# DKBLE112_IO_Shield_v1_0.net
KiCad netlist of a schematic drawn in EAGLE
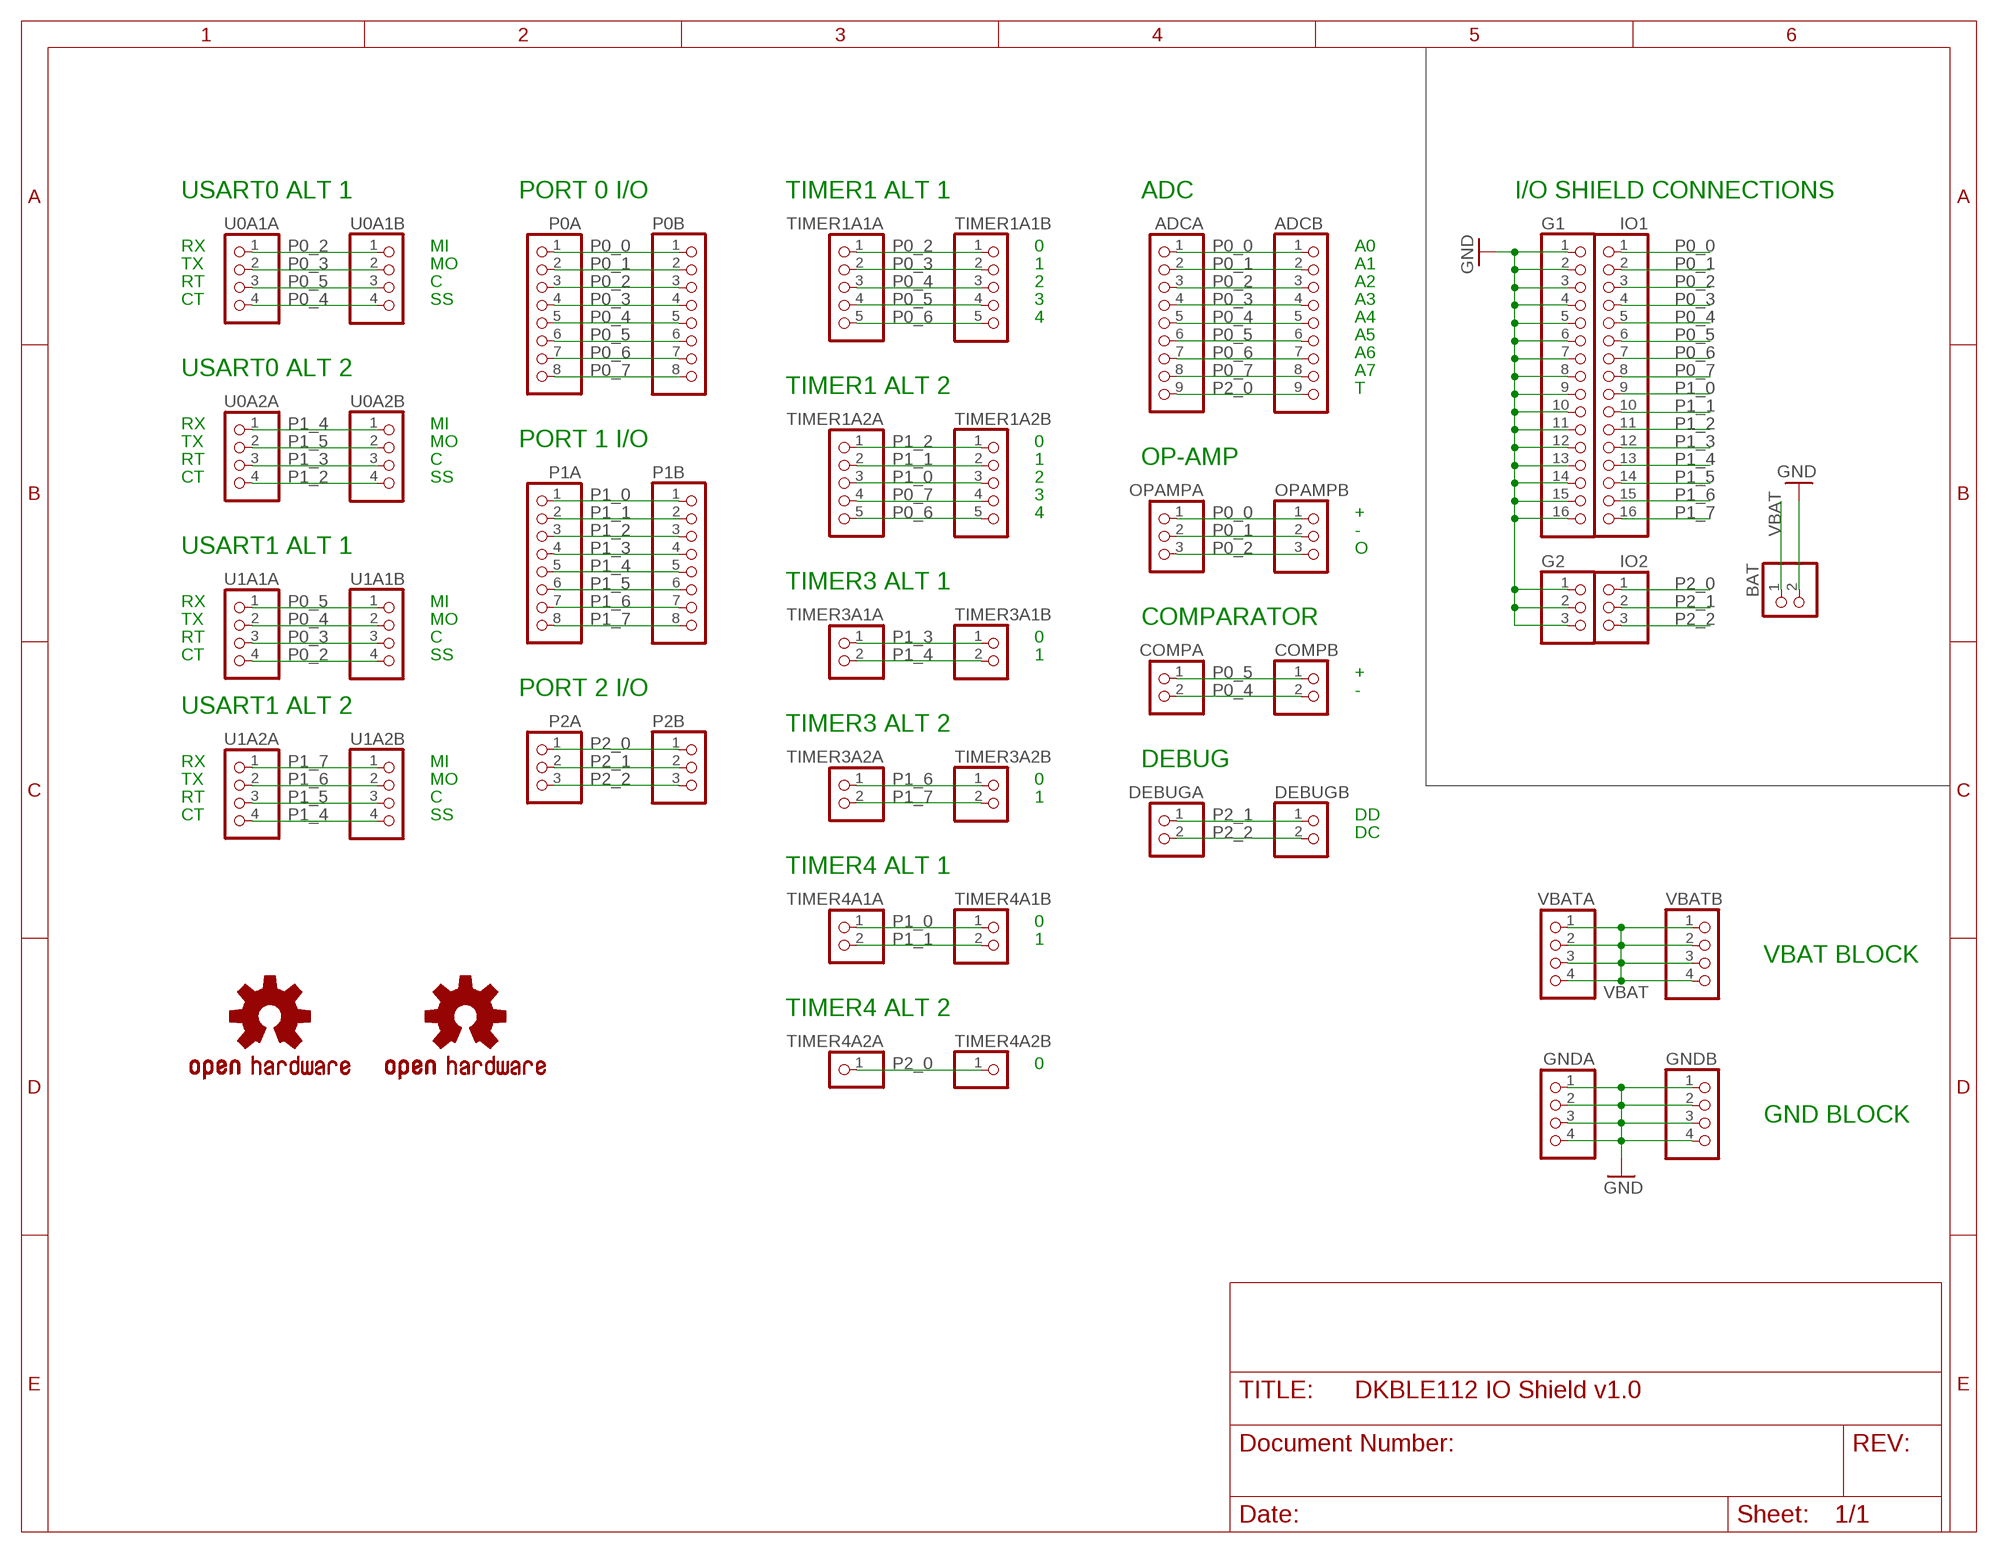
[diagram p0: schematic, sheet 1]

(export (version "E")
  (design (tool "Eeschema 10.0.6"))
  (components
    (comp (ref "ADCA")
      (value "PINHD-1X9")
      (footprint "eagle-import:1X09")
      (libsource (lib "eagle-import") (part "PINHD-1X9"))
    )
    (comp (ref "ADCB")
      (value "PINHD-1X9")
      (footprint "eagle-import:1X09")
      (libsource (lib "eagle-import") (part "PINHD-1X9"))
    )
    (comp (ref "BAT")
      (value "PINHD-1X2")
      (footprint "eagle-import:1X02")
      (libsource (lib "eagle-import") (part "PINHD-1X2"))
    )
    (comp (ref "COMPA")
      (value "PINHD-1X2")
      (footprint "eagle-import:1X02")
      (libsource (lib "eagle-import") (part "PINHD-1X2"))
    )
    (comp (ref "COMPB")
      (value "PINHD-1X2")
      (footprint "eagle-import:1X02")
      (libsource (lib "eagle-import") (part "PINHD-1X2"))
    )
    (comp (ref "DEBUGA")
      (value "PINHD-1X2")
      (footprint "eagle-import:1X02")
      (libsource (lib "eagle-import") (part "PINHD-1X2"))
    )
    (comp (ref "DEBUGB")
      (value "PINHD-1X2")
      (footprint "eagle-import:1X02")
      (libsource (lib "eagle-import") (part "PINHD-1X2"))
    )
    (comp (ref "G1")
      (value "PINHD-1X16")
      (footprint "eagle-import:1X16")
      (libsource (lib "eagle-import") (part "PINHD-1X16"))
    )
    (comp (ref "G2")
      (value "PINHD-1X3")
      (footprint "eagle-import:1X03")
      (libsource (lib "eagle-import") (part "PINHD-1X3"))
    )
    (comp (ref "GNDA")
      (value "PINHD-1X4")
      (footprint "eagle-import:1X04")
      (libsource (lib "eagle-import") (part "PINHD-1X4"))
    )
    (comp (ref "GNDB")
      (value "PINHD-1X4")
      (footprint "eagle-import:1X04")
      (libsource (lib "eagle-import") (part "PINHD-1X4"))
    )
    (comp (ref "IO1")
      (value "PINHD-1X16")
      (footprint "eagle-import:1X16")
      (libsource (lib "eagle-import") (part "PINHD-1X16"))
    )
    (comp (ref "IO2")
      (value "PINHD-1X3")
      (footprint "eagle-import:1X03")
      (libsource (lib "eagle-import") (part "PINHD-1X3"))
    )
    (comp (ref "OPAMPA")
      (value "PINHD-1X3")
      (footprint "eagle-import:1X03")
      (libsource (lib "eagle-import") (part "PINHD-1X3"))
    )
    (comp (ref "OPAMPB")
      (value "PINHD-1X3")
      (footprint "eagle-import:1X03")
      (libsource (lib "eagle-import") (part "PINHD-1X3"))
    )
    (comp (ref "P0A")
      (value "PINHD-1X8")
      (footprint "eagle-import:1X08")
      (libsource (lib "eagle-import") (part "PINHD-1X8"))
    )
    (comp (ref "P0B")
      (value "PINHD-1X8")
      (footprint "eagle-import:1X08")
      (libsource (lib "eagle-import") (part "PINHD-1X8"))
    )
    (comp (ref "P1A")
      (value "PINHD-1X8")
      (footprint "eagle-import:1X08")
      (libsource (lib "eagle-import") (part "PINHD-1X8"))
    )
    (comp (ref "P1B")
      (value "PINHD-1X8")
      (footprint "eagle-import:1X08")
      (libsource (lib "eagle-import") (part "PINHD-1X8"))
    )
    (comp (ref "P2A")
      (value "PINHD-1X3")
      (footprint "eagle-import:1X03")
      (libsource (lib "eagle-import") (part "PINHD-1X3"))
    )
    (comp (ref "P2B")
      (value "PINHD-1X3")
      (footprint "eagle-import:1X03")
      (libsource (lib "eagle-import") (part "PINHD-1X3"))
    )
    (comp (ref "TIMER1A1A")
      (value "PINHD-1X5")
      (footprint "eagle-import:1X05")
      (libsource (lib "eagle-import") (part "PINHD-1X5"))
    )
    (comp (ref "TIMER1A1B")
      (value "PINHD-1X5")
      (footprint "eagle-import:1X05")
      (libsource (lib "eagle-import") (part "PINHD-1X5"))
    )
    (comp (ref "TIMER1A2A")
      (value "PINHD-1X5")
      (footprint "eagle-import:1X05")
      (libsource (lib "eagle-import") (part "PINHD-1X5"))
    )
    (comp (ref "TIMER1A2B")
      (value "PINHD-1X5")
      (footprint "eagle-import:1X05")
      (libsource (lib "eagle-import") (part "PINHD-1X5"))
    )
    (comp (ref "TIMER3A1A")
      (value "PINHD-1X2")
      (footprint "eagle-import:1X02")
      (libsource (lib "eagle-import") (part "PINHD-1X2"))
    )
    (comp (ref "TIMER3A1B")
      (value "PINHD-1X2")
      (footprint "eagle-import:1X02")
      (libsource (lib "eagle-import") (part "PINHD-1X2"))
    )
    (comp (ref "TIMER3A2A")
      (value "PINHD-1X2")
      (footprint "eagle-import:1X02")
      (libsource (lib "eagle-import") (part "PINHD-1X2"))
    )
    (comp (ref "TIMER3A2B")
      (value "PINHD-1X2")
      (footprint "eagle-import:1X02")
      (libsource (lib "eagle-import") (part "PINHD-1X2"))
    )
    (comp (ref "TIMER4A1A")
      (value "PINHD-1X2")
      (footprint "eagle-import:1X02")
      (libsource (lib "eagle-import") (part "PINHD-1X2"))
    )
    (comp (ref "TIMER4A1B")
      (value "PINHD-1X2")
      (footprint "eagle-import:1X02")
      (libsource (lib "eagle-import") (part "PINHD-1X2"))
    )
    (comp (ref "TIMER4A2A")
      (value "PINHD-1X1")
      (footprint "eagle-import:1X01")
      (libsource (lib "eagle-import") (part "PINHD-1X1"))
    )
    (comp (ref "TIMER4A2B")
      (value "PINHD-1X1")
      (footprint "eagle-import:1X01")
      (libsource (lib "eagle-import") (part "PINHD-1X1"))
    )
    (comp (ref "U$1")
      (value "OSHW-LOGOL")
      (footprint "eagle-import:OSHW-LOGO-L")
      (libsource (lib "eagle-import") (part "OSHW-LOGOL"))
    )
    (comp (ref "U$2")
      (value "OSHW-LOGOM")
      (footprint "eagle-import:OSHW-LOGO-M")
      (libsource (lib "eagle-import") (part "OSHW-LOGOM"))
    )
    (comp (ref "U0A1A")
      (value "PINHD-1X4")
      (footprint "eagle-import:1X04")
      (libsource (lib "eagle-import") (part "PINHD-1X4"))
    )
    (comp (ref "U0A1B")
      (value "PINHD-1X4")
      (footprint "eagle-import:1X04")
      (libsource (lib "eagle-import") (part "PINHD-1X4"))
    )
    (comp (ref "U0A2A")
      (value "PINHD-1X4")
      (footprint "eagle-import:1X04")
      (libsource (lib "eagle-import") (part "PINHD-1X4"))
    )
    (comp (ref "U0A2B")
      (value "PINHD-1X4")
      (footprint "eagle-import:1X04")
      (libsource (lib "eagle-import") (part "PINHD-1X4"))
    )
    (comp (ref "U1A1A")
      (value "PINHD-1X4")
      (footprint "eagle-import:1X04")
      (libsource (lib "eagle-import") (part "PINHD-1X4"))
    )
    (comp (ref "U1A1B")
      (value "PINHD-1X4")
      (footprint "eagle-import:1X04")
      (libsource (lib "eagle-import") (part "PINHD-1X4"))
    )
    (comp (ref "U1A2A")
      (value "PINHD-1X4")
      (footprint "eagle-import:1X04")
      (libsource (lib "eagle-import") (part "PINHD-1X4"))
    )
    (comp (ref "U1A2B")
      (value "PINHD-1X4")
      (footprint "eagle-import:1X04")
      (libsource (lib "eagle-import") (part "PINHD-1X4"))
    )
    (comp (ref "VBATA")
      (value "PINHD-1X4")
      (footprint "eagle-import:1X04")
      (libsource (lib "eagle-import") (part "PINHD-1X4"))
    )
    (comp (ref "VBATB")
      (value "PINHD-1X4")
      (footprint "eagle-import:1X04")
      (libsource (lib "eagle-import") (part "PINHD-1X4"))
    )
  )
  (nets
    (net (code "1") (name "/P0_0") (class "Default")
      (node (ref "ADCA") (pin "1") (pinfunction "1_1") (pintype "passive"))
      (node (ref "ADCB") (pin "1") (pinfunction "1_1") (pintype "passive"))
      (node (ref "IO1") (pin "1") (pinfunction "1_1") (pintype "passive"))
      (node (ref "OPAMPA") (pin "1") (pinfunction "1_1") (pintype "passive"))
      (node (ref "OPAMPB") (pin "1") (pinfunction "1_1") (pintype "passive"))
      (node (ref "P0A") (pin "1") (pinfunction "1_1") (pintype "passive"))
      (node (ref "P0B") (pin "1") (pinfunction "1_1") (pintype "passive"))
    )
    (net (code "2") (name "/P0_1") (class "Default")
      (node (ref "ADCA") (pin "2") (pinfunction "2_2") (pintype "passive"))
      (node (ref "ADCB") (pin "2") (pinfunction "2_2") (pintype "passive"))
      (node (ref "IO1") (pin "2") (pinfunction "2_2") (pintype "passive"))
      (node (ref "OPAMPA") (pin "2") (pinfunction "2_2") (pintype "passive"))
      (node (ref "OPAMPB") (pin "2") (pinfunction "2_2") (pintype "passive"))
      (node (ref "P0A") (pin "2") (pinfunction "2_2") (pintype "passive"))
      (node (ref "P0B") (pin "2") (pinfunction "2_2") (pintype "passive"))
    )
    (net (code "3") (name "/P0_2") (class "Default")
      (node (ref "ADCA") (pin "3") (pinfunction "3_3") (pintype "passive"))
      (node (ref "ADCB") (pin "3") (pinfunction "3_3") (pintype "passive"))
      (node (ref "IO1") (pin "3") (pinfunction "3_3") (pintype "passive"))
      (node (ref "OPAMPA") (pin "3") (pinfunction "3_3") (pintype "passive"))
      (node (ref "OPAMPB") (pin "3") (pinfunction "3_3") (pintype "passive"))
      (node (ref "P0A") (pin "3") (pinfunction "3_3") (pintype "passive"))
      (node (ref "P0B") (pin "3") (pinfunction "3_3") (pintype "passive"))
      (node (ref "TIMER1A1A") (pin "1") (pinfunction "1_1") (pintype "passive"))
      (node (ref "TIMER1A1B") (pin "1") (pinfunction "1_1") (pintype "passive"))
      (node (ref "U0A1A") (pin "1") (pinfunction "1_1") (pintype "passive"))
      (node (ref "U0A1B") (pin "1") (pinfunction "1_1") (pintype "passive"))
      (node (ref "U1A1A") (pin "4") (pinfunction "4_4") (pintype "passive"))
      (node (ref "U1A1B") (pin "4") (pinfunction "4_4") (pintype "passive"))
    )
    (net (code "4") (name "/P0_3") (class "Default")
      (node (ref "ADCA") (pin "4") (pinfunction "4_4") (pintype "passive"))
      (node (ref "ADCB") (pin "4") (pinfunction "4_4") (pintype "passive"))
      (node (ref "IO1") (pin "4") (pinfunction "4_4") (pintype "passive"))
      (node (ref "P0A") (pin "4") (pinfunction "4_4") (pintype "passive"))
      (node (ref "P0B") (pin "4") (pinfunction "4_4") (pintype "passive"))
      (node (ref "TIMER1A1A") (pin "2") (pinfunction "2_2") (pintype "passive"))
      (node (ref "TIMER1A1B") (pin "2") (pinfunction "2_2") (pintype "passive"))
      (node (ref "U0A1A") (pin "2") (pinfunction "2_2") (pintype "passive"))
      (node (ref "U0A1B") (pin "2") (pinfunction "2_2") (pintype "passive"))
      (node (ref "U1A1A") (pin "3") (pinfunction "3_3") (pintype "passive"))
      (node (ref "U1A1B") (pin "3") (pinfunction "3_3") (pintype "passive"))
    )
    (net (code "5") (name "/P0_4") (class "Default")
      (node (ref "ADCA") (pin "5") (pinfunction "5_5") (pintype "passive"))
      (node (ref "ADCB") (pin "5") (pinfunction "5_5") (pintype "passive"))
      (node (ref "COMPA") (pin "2") (pinfunction "2_2") (pintype "passive"))
      (node (ref "COMPB") (pin "2") (pinfunction "2_2") (pintype "passive"))
      (node (ref "IO1") (pin "5") (pinfunction "5_5") (pintype "passive"))
      (node (ref "P0A") (pin "5") (pinfunction "5_5") (pintype "passive"))
      (node (ref "P0B") (pin "5") (pinfunction "5_5") (pintype "passive"))
      (node (ref "TIMER1A1A") (pin "3") (pinfunction "3_3") (pintype "passive"))
      (node (ref "TIMER1A1B") (pin "3") (pinfunction "3_3") (pintype "passive"))
      (node (ref "U0A1A") (pin "4") (pinfunction "4_4") (pintype "passive"))
      (node (ref "U0A1B") (pin "4") (pinfunction "4_4") (pintype "passive"))
      (node (ref "U1A1A") (pin "2") (pinfunction "2_2") (pintype "passive"))
      (node (ref "U1A1B") (pin "2") (pinfunction "2_2") (pintype "passive"))
    )
    (net (code "6") (name "/P0_5") (class "Default")
      (node (ref "ADCA") (pin "6") (pinfunction "6_6") (pintype "passive"))
      (node (ref "ADCB") (pin "6") (pinfunction "6_6") (pintype "passive"))
      (node (ref "COMPA") (pin "1") (pinfunction "1_1") (pintype "passive"))
      (node (ref "COMPB") (pin "1") (pinfunction "1_1") (pintype "passive"))
      (node (ref "IO1") (pin "6") (pinfunction "6_6") (pintype "passive"))
      (node (ref "P0A") (pin "6") (pinfunction "6_6") (pintype "passive"))
      (node (ref "P0B") (pin "6") (pinfunction "6_6") (pintype "passive"))
      (node (ref "TIMER1A1A") (pin "4") (pinfunction "4_4") (pintype "passive"))
      (node (ref "TIMER1A1B") (pin "4") (pinfunction "4_4") (pintype "passive"))
      (node (ref "U0A1A") (pin "3") (pinfunction "3_3") (pintype "passive"))
      (node (ref "U0A1B") (pin "3") (pinfunction "3_3") (pintype "passive"))
      (node (ref "U1A1A") (pin "1") (pinfunction "1_1") (pintype "passive"))
      (node (ref "U1A1B") (pin "1") (pinfunction "1_1") (pintype "passive"))
    )
    (net (code "7") (name "/P0_6") (class "Default")
      (node (ref "ADCA") (pin "7") (pinfunction "7_7") (pintype "passive"))
      (node (ref "ADCB") (pin "7") (pinfunction "7_7") (pintype "passive"))
      (node (ref "IO1") (pin "7") (pinfunction "7_7") (pintype "passive"))
      (node (ref "P0A") (pin "7") (pinfunction "7_7") (pintype "passive"))
      (node (ref "P0B") (pin "7") (pinfunction "7_7") (pintype "passive"))
      (node (ref "TIMER1A1A") (pin "5") (pinfunction "5_5") (pintype "passive"))
      (node (ref "TIMER1A1B") (pin "5") (pinfunction "5_5") (pintype "passive"))
      (node (ref "TIMER1A2A") (pin "5") (pinfunction "5_5") (pintype "passive"))
      (node (ref "TIMER1A2B") (pin "5") (pinfunction "5_5") (pintype "passive"))
    )
    (net (code "8") (name "/P0_7") (class "Default")
      (node (ref "ADCA") (pin "8") (pinfunction "8_8") (pintype "passive"))
      (node (ref "ADCB") (pin "8") (pinfunction "8_8") (pintype "passive"))
      (node (ref "IO1") (pin "8") (pinfunction "8_8") (pintype "passive"))
      (node (ref "P0A") (pin "8") (pinfunction "8_8") (pintype "passive"))
      (node (ref "P0B") (pin "8") (pinfunction "8_8") (pintype "passive"))
      (node (ref "TIMER1A2A") (pin "4") (pinfunction "4_4") (pintype "passive"))
      (node (ref "TIMER1A2B") (pin "4") (pinfunction "4_4") (pintype "passive"))
    )
    (net (code "9") (name "/P1_0") (class "Default")
      (node (ref "IO1") (pin "9") (pinfunction "9_9") (pintype "passive"))
      (node (ref "P1A") (pin "1") (pinfunction "1_1") (pintype "passive"))
      (node (ref "P1B") (pin "1") (pinfunction "1_1") (pintype "passive"))
      (node (ref "TIMER1A2A") (pin "3") (pinfunction "3_3") (pintype "passive"))
      (node (ref "TIMER1A2B") (pin "3") (pinfunction "3_3") (pintype "passive"))
      (node (ref "TIMER4A1A") (pin "1") (pinfunction "1_1") (pintype "passive"))
      (node (ref "TIMER4A1B") (pin "1") (pinfunction "1_1") (pintype "passive"))
    )
    (net (code "10") (name "/P1_1") (class "Default")
      (node (ref "IO1") (pin "10") (pinfunction "10_10") (pintype "passive"))
      (node (ref "P1A") (pin "2") (pinfunction "2_2") (pintype "passive"))
      (node (ref "P1B") (pin "2") (pinfunction "2_2") (pintype "passive"))
      (node (ref "TIMER1A2A") (pin "2") (pinfunction "2_2") (pintype "passive"))
      (node (ref "TIMER1A2B") (pin "2") (pinfunction "2_2") (pintype "passive"))
      (node (ref "TIMER4A1A") (pin "2") (pinfunction "2_2") (pintype "passive"))
      (node (ref "TIMER4A1B") (pin "2") (pinfunction "2_2") (pintype "passive"))
    )
    (net (code "11") (name "/P1_2") (class "Default")
      (node (ref "IO1") (pin "11") (pinfunction "11_11") (pintype "passive"))
      (node (ref "P1A") (pin "3") (pinfunction "3_3") (pintype "passive"))
      (node (ref "P1B") (pin "3") (pinfunction "3_3") (pintype "passive"))
      (node (ref "TIMER1A2A") (pin "1") (pinfunction "1_1") (pintype "passive"))
      (node (ref "TIMER1A2B") (pin "1") (pinfunction "1_1") (pintype "passive"))
      (node (ref "U0A2A") (pin "4") (pinfunction "4_4") (pintype "passive"))
      (node (ref "U0A2B") (pin "4") (pinfunction "4_4") (pintype "passive"))
    )
    (net (code "12") (name "/P1_3") (class "Default")
      (node (ref "IO1") (pin "12") (pinfunction "12_12") (pintype "passive"))
      (node (ref "P1A") (pin "4") (pinfunction "4_4") (pintype "passive"))
      (node (ref "P1B") (pin "4") (pinfunction "4_4") (pintype "passive"))
      (node (ref "TIMER3A1A") (pin "1") (pinfunction "1_1") (pintype "passive"))
      (node (ref "TIMER3A1B") (pin "1") (pinfunction "1_1") (pintype "passive"))
      (node (ref "U0A2A") (pin "3") (pinfunction "3_3") (pintype "passive"))
      (node (ref "U0A2B") (pin "3") (pinfunction "3_3") (pintype "passive"))
    )
    (net (code "13") (name "/P1_4") (class "Default")
      (node (ref "IO1") (pin "13") (pinfunction "13_13") (pintype "passive"))
      (node (ref "P1A") (pin "5") (pinfunction "5_5") (pintype "passive"))
      (node (ref "P1B") (pin "5") (pinfunction "5_5") (pintype "passive"))
      (node (ref "TIMER3A1A") (pin "2") (pinfunction "2_2") (pintype "passive"))
      (node (ref "TIMER3A1B") (pin "2") (pinfunction "2_2") (pintype "passive"))
      (node (ref "U0A2A") (pin "1") (pinfunction "1_1") (pintype "passive"))
      (node (ref "U0A2B") (pin "1") (pinfunction "1_1") (pintype "passive"))
      (node (ref "U1A2A") (pin "4") (pinfunction "4_4") (pintype "passive"))
      (node (ref "U1A2B") (pin "4") (pinfunction "4_4") (pintype "passive"))
    )
    (net (code "14") (name "/P1_5") (class "Default")
      (node (ref "IO1") (pin "14") (pinfunction "14_14") (pintype "passive"))
      (node (ref "P1A") (pin "6") (pinfunction "6_6") (pintype "passive"))
      (node (ref "P1B") (pin "6") (pinfunction "6_6") (pintype "passive"))
      (node (ref "U0A2A") (pin "2") (pinfunction "2_2") (pintype "passive"))
      (node (ref "U0A2B") (pin "2") (pinfunction "2_2") (pintype "passive"))
      (node (ref "U1A2A") (pin "3") (pinfunction "3_3") (pintype "passive"))
      (node (ref "U1A2B") (pin "3") (pinfunction "3_3") (pintype "passive"))
    )
    (net (code "15") (name "/P1_6") (class "Default")
      (node (ref "IO1") (pin "15") (pinfunction "15_15") (pintype "passive"))
      (node (ref "P1A") (pin "7") (pinfunction "7_7") (pintype "passive"))
      (node (ref "P1B") (pin "7") (pinfunction "7_7") (pintype "passive"))
      (node (ref "TIMER3A2A") (pin "1") (pinfunction "1_1") (pintype "passive"))
      (node (ref "TIMER3A2B") (pin "1") (pinfunction "1_1") (pintype "passive"))
      (node (ref "U1A2A") (pin "2") (pinfunction "2_2") (pintype "passive"))
      (node (ref "U1A2B") (pin "2") (pinfunction "2_2") (pintype "passive"))
    )
    (net (code "16") (name "/P1_7") (class "Default")
      (node (ref "IO1") (pin "16") (pinfunction "16_16") (pintype "passive"))
      (node (ref "P1A") (pin "8") (pinfunction "8_8") (pintype "passive"))
      (node (ref "P1B") (pin "8") (pinfunction "8_8") (pintype "passive"))
      (node (ref "TIMER3A2A") (pin "2") (pinfunction "2_2") (pintype "passive"))
      (node (ref "TIMER3A2B") (pin "2") (pinfunction "2_2") (pintype "passive"))
      (node (ref "U1A2A") (pin "1") (pinfunction "1_1") (pintype "passive"))
      (node (ref "U1A2B") (pin "1") (pinfunction "1_1") (pintype "passive"))
    )
    (net (code "17") (name "/P2_0") (class "Default")
      (node (ref "ADCA") (pin "9") (pinfunction "9_9") (pintype "passive"))
      (node (ref "ADCB") (pin "9") (pinfunction "9_9") (pintype "passive"))
      (node (ref "IO2") (pin "1") (pinfunction "1_1") (pintype "passive"))
      (node (ref "P2A") (pin "1") (pinfunction "1_1") (pintype "passive"))
      (node (ref "P2B") (pin "1") (pinfunction "1_1") (pintype "passive"))
      (node (ref "TIMER4A2A") (pin "1") (pinfunction "1_1") (pintype "passive"))
      (node (ref "TIMER4A2B") (pin "1") (pinfunction "1_1") (pintype "passive"))
    )
    (net (code "18") (name "/P2_1") (class "Default")
      (node (ref "DEBUGA") (pin "1") (pinfunction "1_1") (pintype "passive"))
      (node (ref "DEBUGB") (pin "1") (pinfunction "1_1") (pintype "passive"))
      (node (ref "IO2") (pin "2") (pinfunction "2_2") (pintype "passive"))
      (node (ref "P2A") (pin "2") (pinfunction "2_2") (pintype "passive"))
      (node (ref "P2B") (pin "2") (pinfunction "2_2") (pintype "passive"))
    )
    (net (code "19") (name "/P2_2") (class "Default")
      (node (ref "DEBUGA") (pin "2") (pinfunction "2_2") (pintype "passive"))
      (node (ref "DEBUGB") (pin "2") (pinfunction "2_2") (pintype "passive"))
      (node (ref "IO2") (pin "3") (pinfunction "3_3") (pintype "passive"))
      (node (ref "P2A") (pin "3") (pinfunction "3_3") (pintype "passive"))
      (node (ref "P2B") (pin "3") (pinfunction "3_3") (pintype "passive"))
    )
    (net (code "20") (name "/VBAT") (class "Default")
      (node (ref "BAT") (pin "1") (pinfunction "1_1") (pintype "passive"))
      (node (ref "VBATA") (pin "1") (pinfunction "1_1") (pintype "passive"))
      (node (ref "VBATA") (pin "2") (pinfunction "2_2") (pintype "passive"))
      (node (ref "VBATA") (pin "3") (pinfunction "3_3") (pintype "passive"))
      (node (ref "VBATA") (pin "4") (pinfunction "4_4") (pintype "passive"))
      (node (ref "VBATB") (pin "1") (pinfunction "1_1") (pintype "passive"))
      (node (ref "VBATB") (pin "2") (pinfunction "2_2") (pintype "passive"))
      (node (ref "VBATB") (pin "3") (pinfunction "3_3") (pintype "passive"))
      (node (ref "VBATB") (pin "4") (pinfunction "4_4") (pintype "passive"))
    )
    (net (code "21") (name "GND") (class "Default")
      (node (ref "BAT") (pin "2") (pinfunction "2_2") (pintype "passive"))
      (node (ref "G1") (pin "1") (pinfunction "1_1") (pintype "passive"))
      (node (ref "G1") (pin "10") (pinfunction "10_10") (pintype "passive"))
      (node (ref "G1") (pin "11") (pinfunction "11_11") (pintype "passive"))
      (node (ref "G1") (pin "12") (pinfunction "12_12") (pintype "passive"))
      (node (ref "G1") (pin "13") (pinfunction "13_13") (pintype "passive"))
      (node (ref "G1") (pin "14") (pinfunction "14_14") (pintype "passive"))
      (node (ref "G1") (pin "15") (pinfunction "15_15") (pintype "passive"))
      (node (ref "G1") (pin "16") (pinfunction "16_16") (pintype "passive"))
      (node (ref "G1") (pin "2") (pinfunction "2_2") (pintype "passive"))
      (node (ref "G1") (pin "3") (pinfunction "3_3") (pintype "passive"))
      (node (ref "G1") (pin "4") (pinfunction "4_4") (pintype "passive"))
      (node (ref "G1") (pin "5") (pinfunction "5_5") (pintype "passive"))
      (node (ref "G1") (pin "6") (pinfunction "6_6") (pintype "passive"))
      (node (ref "G1") (pin "7") (pinfunction "7_7") (pintype "passive"))
      (node (ref "G1") (pin "8") (pinfunction "8_8") (pintype "passive"))
      (node (ref "G1") (pin "9") (pinfunction "9_9") (pintype "passive"))
      (node (ref "G2") (pin "1") (pinfunction "1_1") (pintype "passive"))
      (node (ref "G2") (pin "2") (pinfunction "2_2") (pintype "passive"))
      (node (ref "G2") (pin "3") (pinfunction "3_3") (pintype "passive"))
      (node (ref "GNDA") (pin "1") (pinfunction "1_1") (pintype "passive"))
      (node (ref "GNDA") (pin "2") (pinfunction "2_2") (pintype "passive"))
      (node (ref "GNDA") (pin "3") (pinfunction "3_3") (pintype "passive"))
      (node (ref "GNDA") (pin "4") (pinfunction "4_4") (pintype "passive"))
      (node (ref "GNDB") (pin "1") (pinfunction "1_1") (pintype "passive"))
      (node (ref "GNDB") (pin "2") (pinfunction "2_2") (pintype "passive"))
      (node (ref "GNDB") (pin "3") (pinfunction "3_3") (pintype "passive"))
      (node (ref "GNDB") (pin "4") (pinfunction "4_4") (pintype "passive"))
    )
  )
)
